# uCschematic.net
KiCad netlist of a schematic drawn in EAGLE
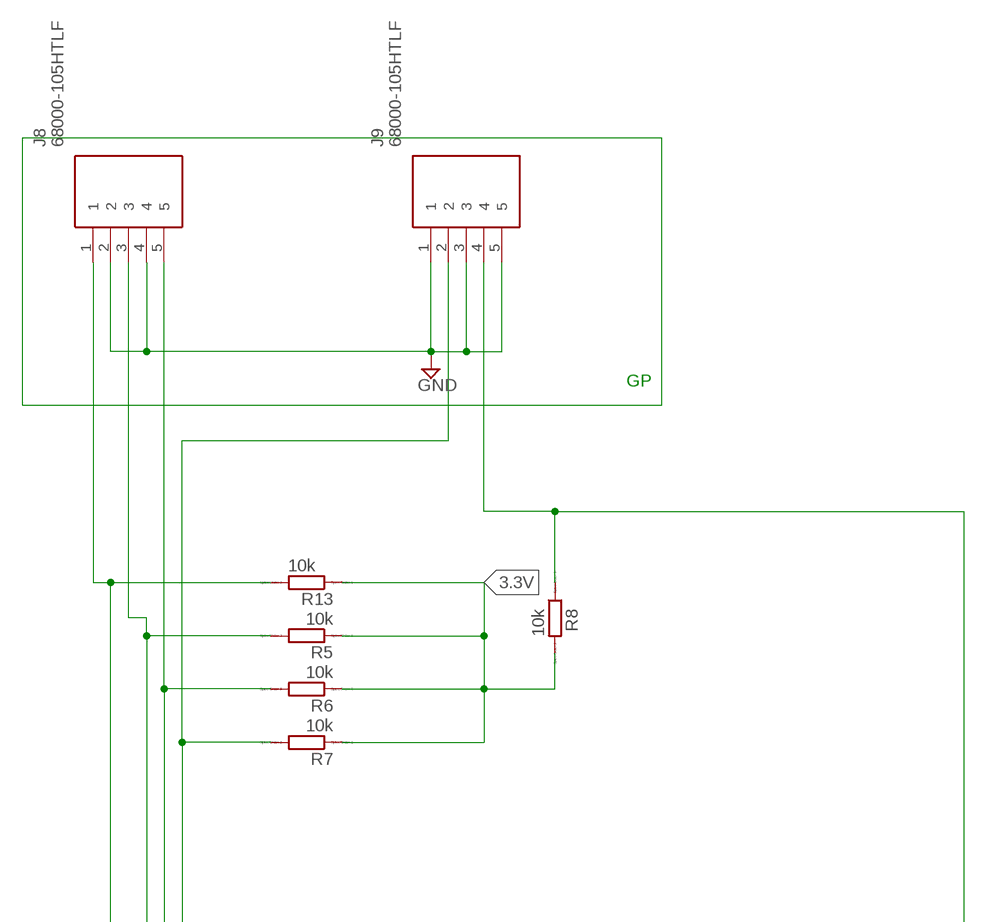
[diagram p0: schematic, sheet 1, part 1 of 3]
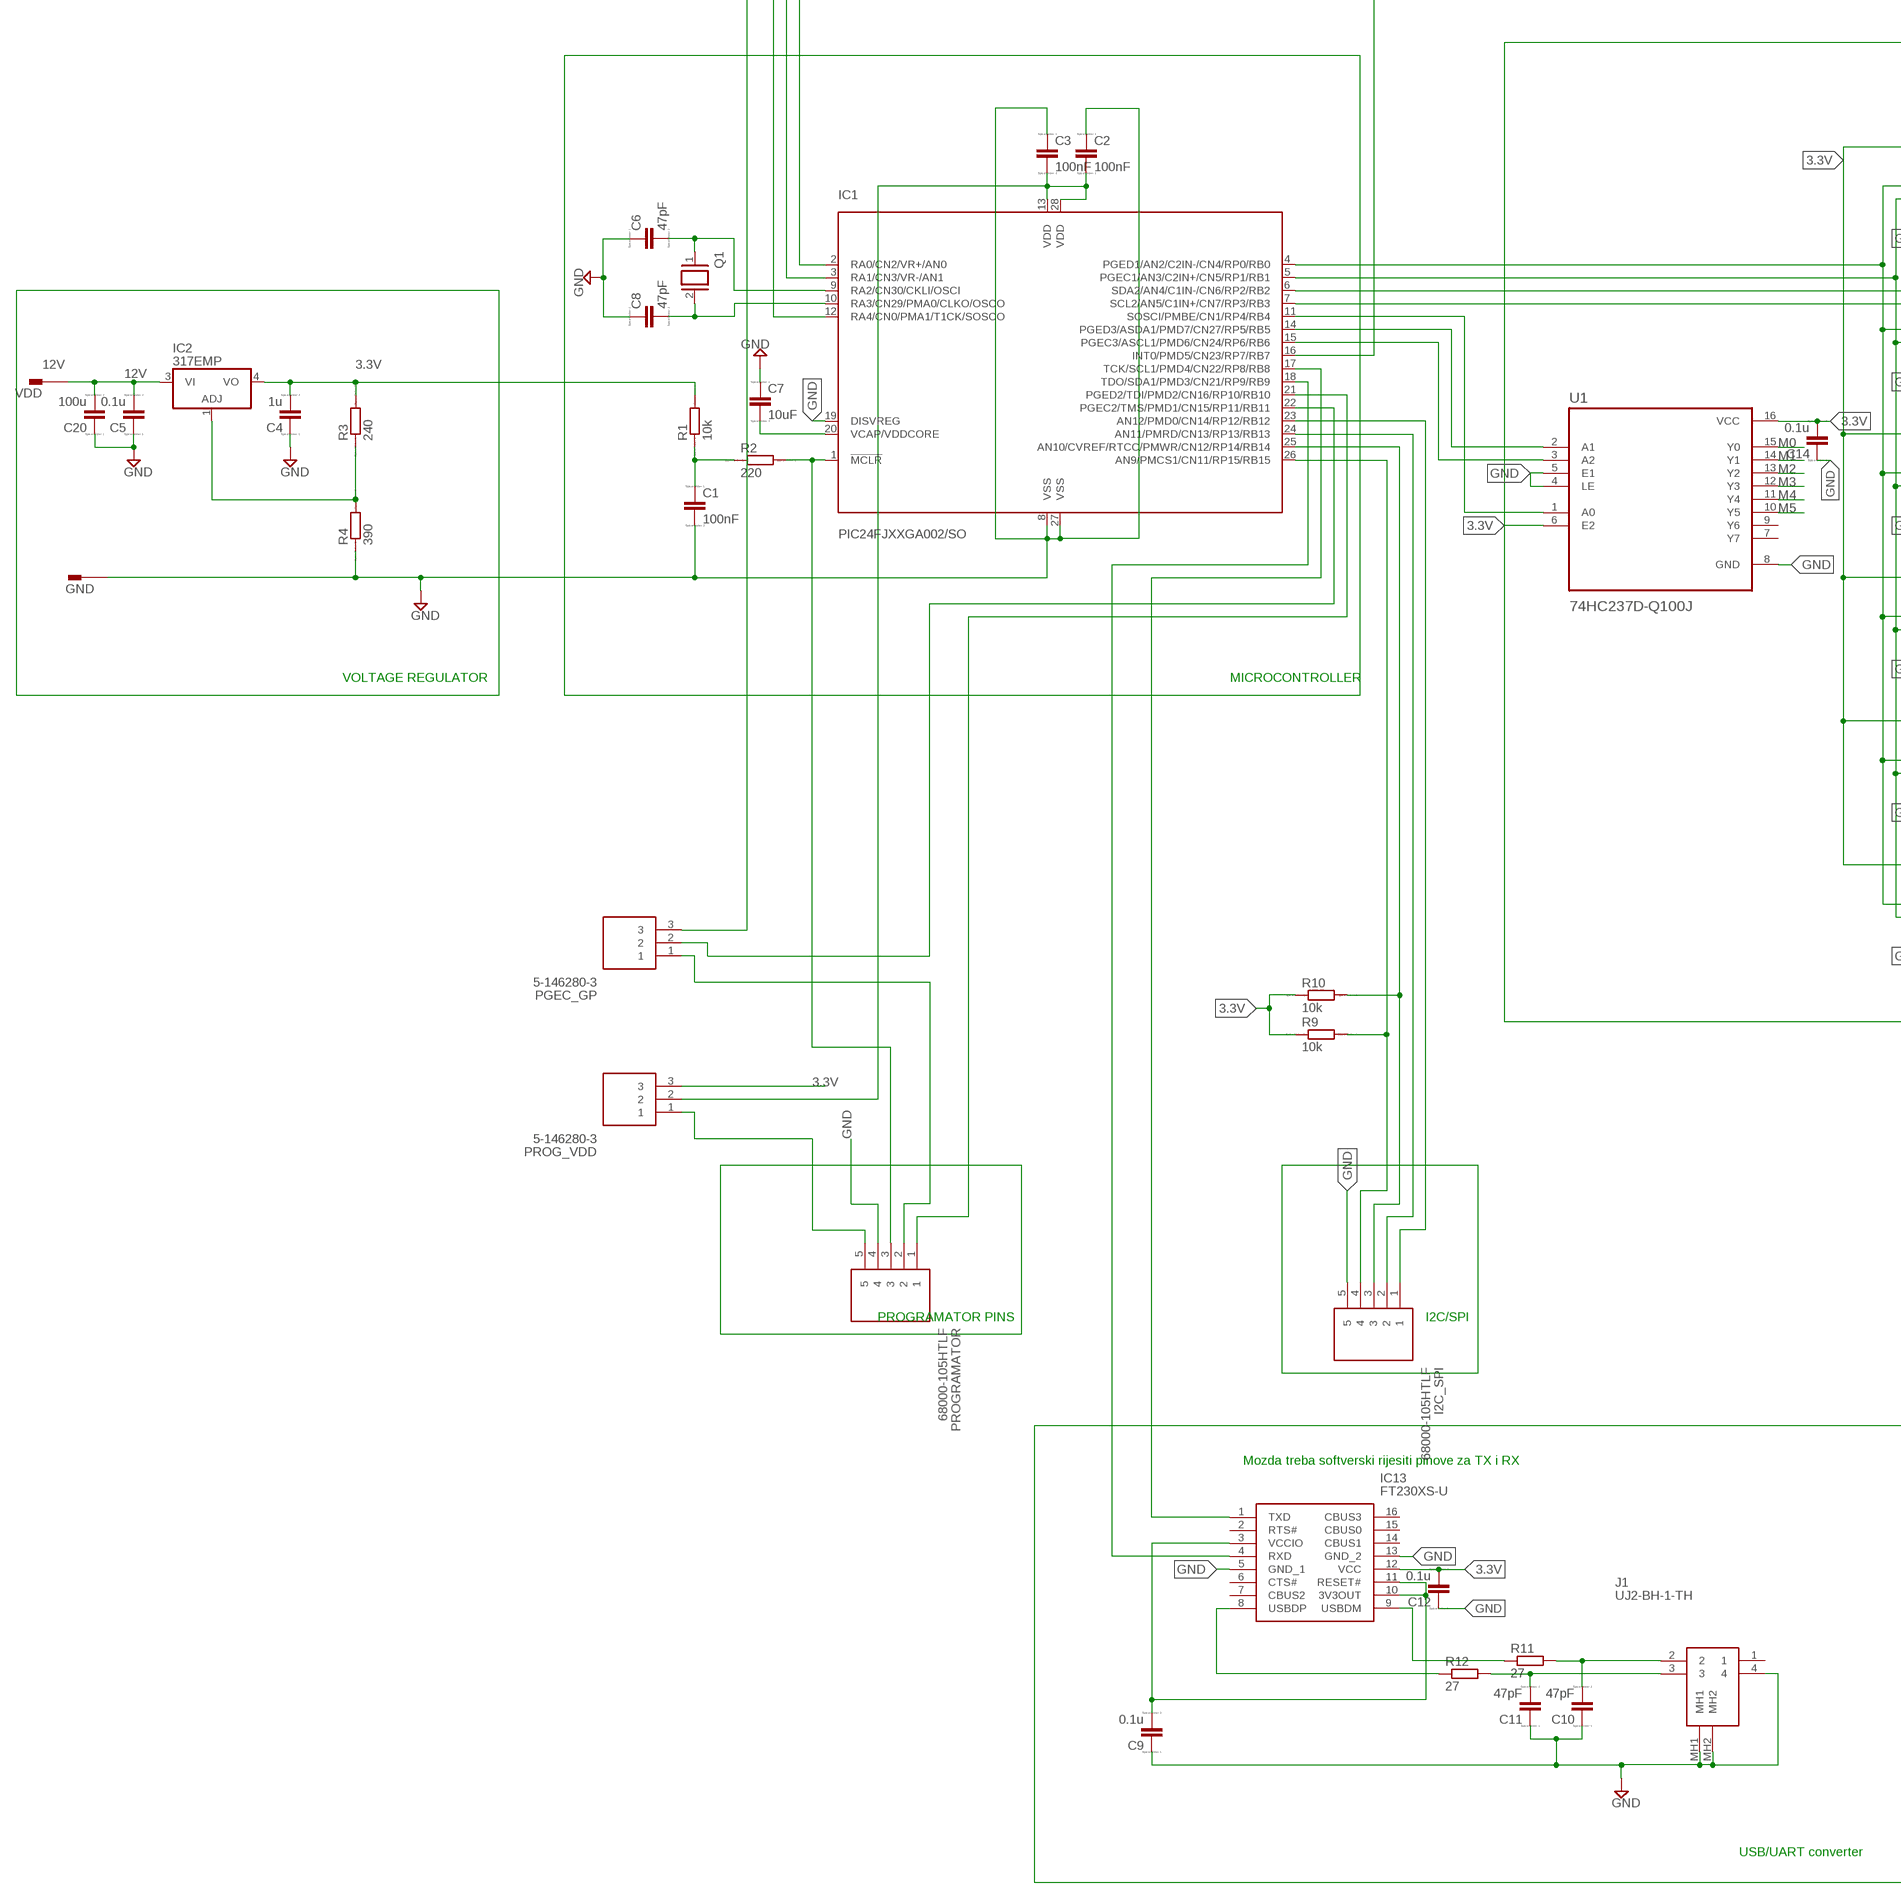
[diagram p1: schematic, sheet 1, part 2 of 3]
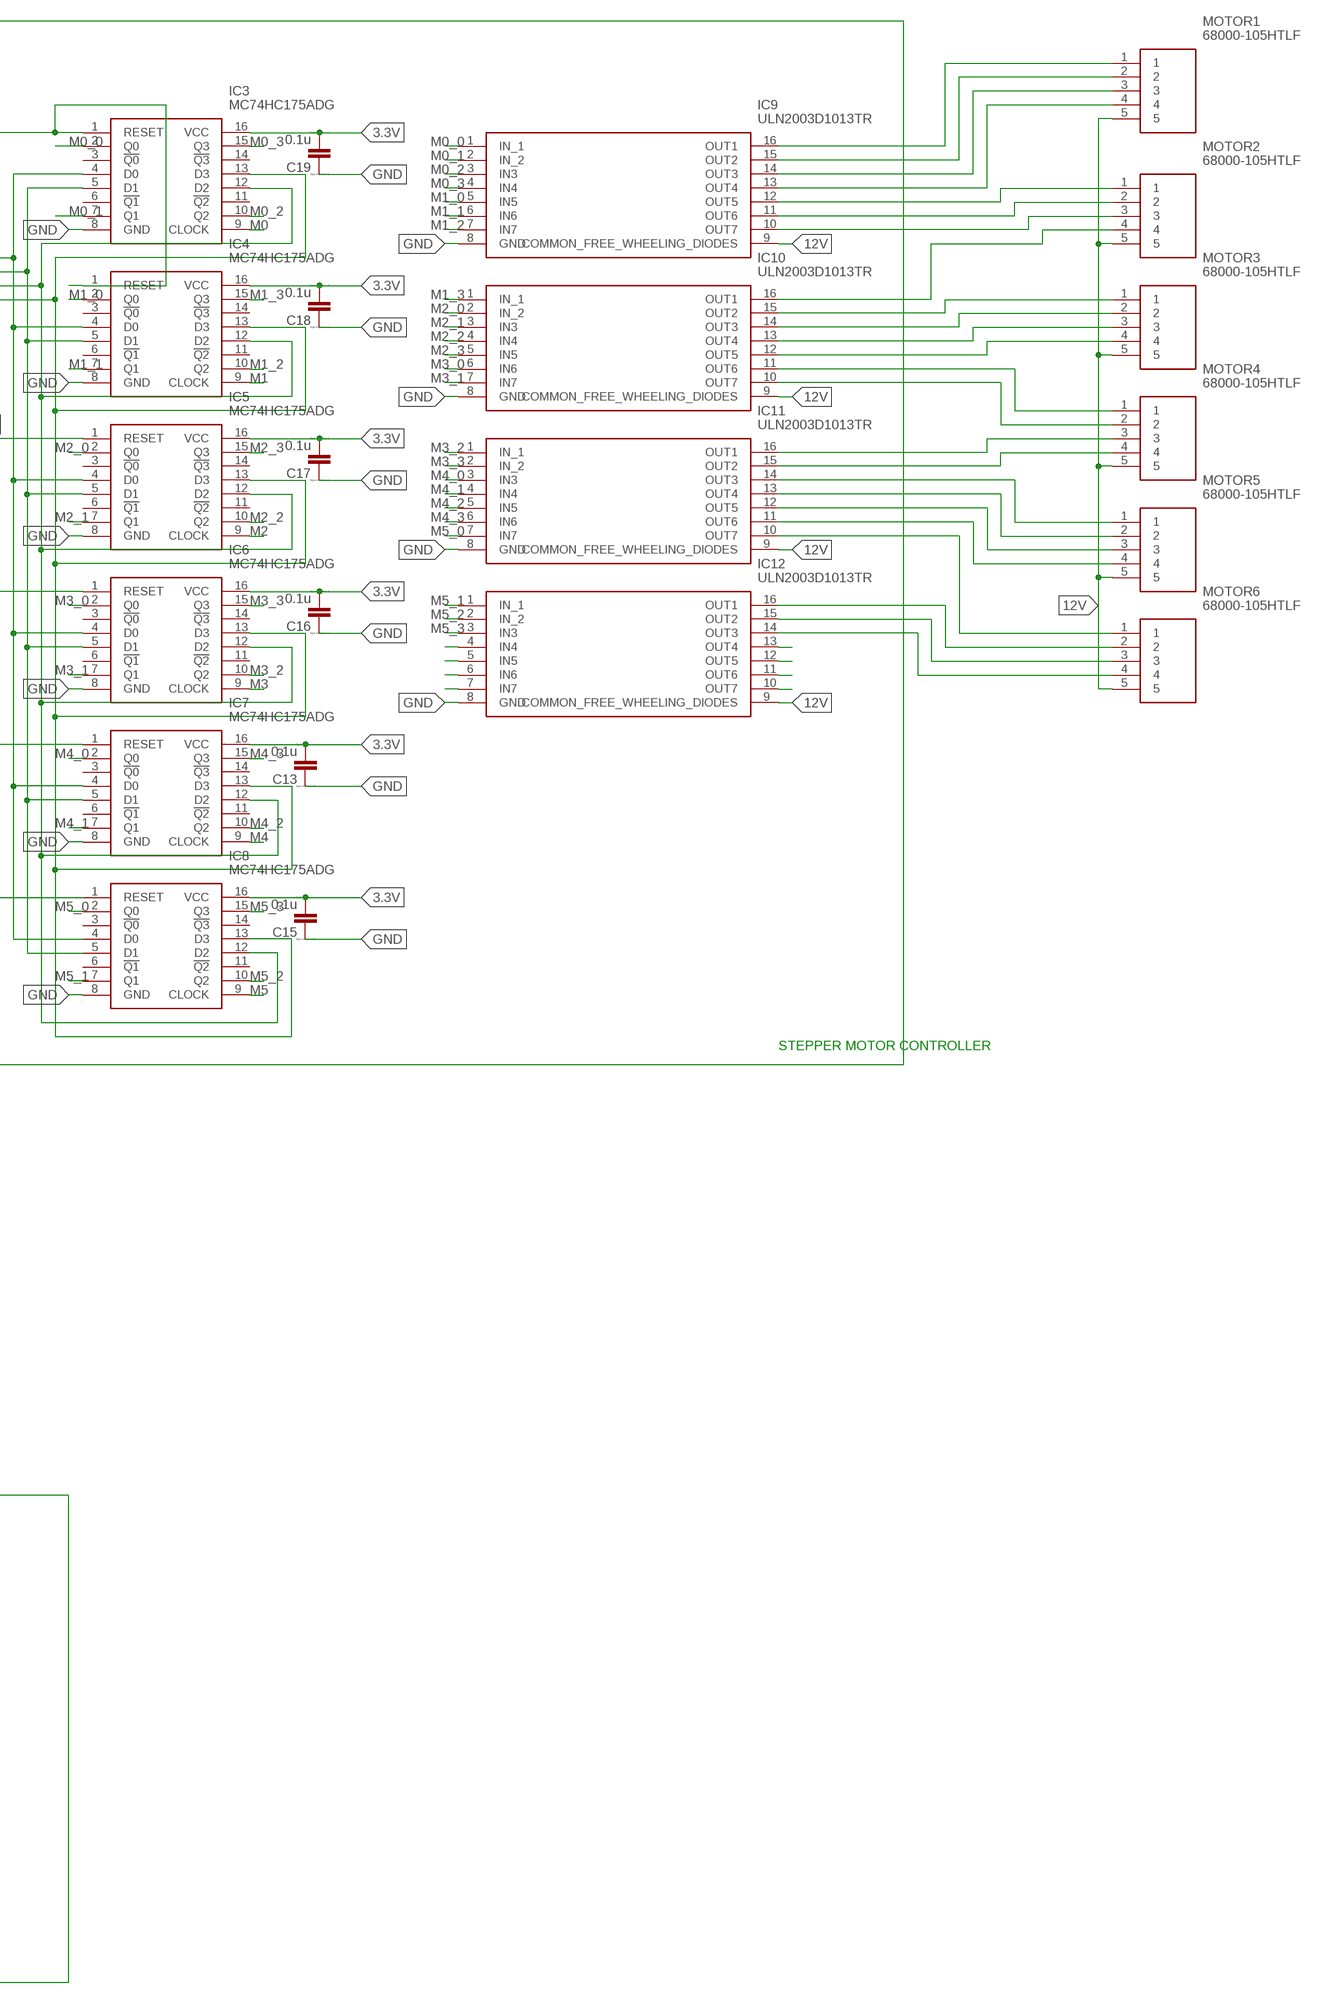
[diagram p2: schematic, sheet 1, part 3 of 3]

(export (version "E")
  (design (tool "Eeschema 10.0.6"))
  (components
    (comp (ref "C1")
      (value "100nF")
      (footprint "eagle-import:C0805")
      (libsource (lib "eagle-import") (part "C"))
    )
    (comp (ref "C2")
      (value "100nF")
      (footprint "eagle-import:C0805")
      (libsource (lib "eagle-import") (part "C"))
    )
    (comp (ref "C3")
      (value "100nF")
      (footprint "eagle-import:C0805")
      (libsource (lib "eagle-import") (part "C"))
    )
    (comp (ref "C4")
      (value "1u")
      (footprint "eagle-import:C0805")
      (libsource (lib "eagle-import") (part "C"))
    )
    (comp (ref "C5")
      (value "0.1u")
      (footprint "eagle-import:C0805")
      (libsource (lib "eagle-import") (part "C"))
    )
    (comp (ref "C6")
      (value "47pF")
      (footprint "eagle-import:C0805")
      (libsource (lib "eagle-import") (part "C"))
    )
    (comp (ref "C7")
      (value "10uF")
      (footprint "eagle-import:C0805")
      (libsource (lib "eagle-import") (part "C"))
    )
    (comp (ref "C8")
      (value "47pF")
      (footprint "eagle-import:C0805")
      (libsource (lib "eagle-import") (part "C"))
    )
    (comp (ref "C9")
      (value "0.1u")
      (footprint "eagle-import:C0805")
      (libsource (lib "eagle-import") (part "C"))
    )
    (comp (ref "C10")
      (value "47pF")
      (footprint "eagle-import:C0805")
      (libsource (lib "eagle-import") (part "C"))
    )
    (comp (ref "C11")
      (value "47pF")
      (footprint "eagle-import:C0805")
      (libsource (lib "eagle-import") (part "C"))
    )
    (comp (ref "C12")
      (value "0.1u")
      (footprint "eagle-import:C0805")
      (libsource (lib "eagle-import") (part "C"))
    )
    (comp (ref "C13")
      (value "0.1u")
      (footprint "eagle-import:C0805")
      (libsource (lib "eagle-import") (part "C"))
    )
    (comp (ref "C14")
      (value "0.1u")
      (footprint "eagle-import:C0805")
      (libsource (lib "eagle-import") (part "C"))
    )
    (comp (ref "C15")
      (value "0.1u")
      (footprint "eagle-import:C0805")
      (libsource (lib "eagle-import") (part "C"))
    )
    (comp (ref "C16")
      (value "0.1u")
      (footprint "eagle-import:C0805")
      (libsource (lib "eagle-import") (part "C"))
    )
    (comp (ref "C17")
      (value "0.1u")
      (footprint "eagle-import:C0805")
      (libsource (lib "eagle-import") (part "C"))
    )
    (comp (ref "C18")
      (value "0.1u")
      (footprint "eagle-import:C0805")
      (libsource (lib "eagle-import") (part "C"))
    )
    (comp (ref "C19")
      (value "0.1u")
      (footprint "eagle-import:C0805")
      (libsource (lib "eagle-import") (part "C"))
    )
    (comp (ref "C20")
      (value "100u")
      (footprint "eagle-import:C0805")
      (libsource (lib "eagle-import") (part "C"))
    )
    (comp (ref "GND")
      (value "PIN1-2")
      (footprint "eagle-import:62221")
      (fields (field (name "MF") "TYCO ELECTRONICS") (field (name "MPN") "62221-1"))
      (libsource (lib "eagle-import") (part "PIN1-2"))
    )
    (comp (ref "I2C_SPI")
      (value "68000-105HTLF")
      (footprint "eagle-import:HDRV5W67P0X254_1X5_1270X241X85")
      (fields (field (name "MOUSER_PART_NUMBER") "649-68000-105HTLF"))
      (libsource (lib "eagle-import") (part "68000-105HTLF"))
    )
    (comp (ref "IC1")
      (value "PIC24FJXXGA002/SO")
      (footprint "eagle-import:SO28W")
      (libsource (lib "eagle-import") (part "PIC24FJXXGA002/SO"))
    )
    (comp (ref "IC2")
      (value "317EMP")
      (footprint "eagle-import:SOT223")
      (libsource (lib "eagle-import") (part "317EMP"))
    )
    (comp (ref "IC3")
      (value "MC74HC175ADG")
      (footprint "eagle-import:SOIC127P600X175-16N")
      (fields (field (name "MOUSER_PART_NUMBER") "863-MC74HC175ADG"))
      (libsource (lib "eagle-import") (part "MC74HC175ADG"))
    )
    (comp (ref "IC4")
      (value "MC74HC175ADG")
      (footprint "eagle-import:SOIC127P600X175-16N")
      (fields (field (name "MOUSER_PART_NUMBER") "863-MC74HC175ADG"))
      (libsource (lib "eagle-import") (part "MC74HC175ADG"))
    )
    (comp (ref "IC5")
      (value "MC74HC175ADG")
      (footprint "eagle-import:SOIC127P600X175-16N")
      (fields (field (name "MOUSER_PART_NUMBER") "863-MC74HC175ADG"))
      (libsource (lib "eagle-import") (part "MC74HC175ADG"))
    )
    (comp (ref "IC6")
      (value "MC74HC175ADG")
      (footprint "eagle-import:SOIC127P600X175-16N")
      (fields (field (name "MOUSER_PART_NUMBER") "863-MC74HC175ADG"))
      (libsource (lib "eagle-import") (part "MC74HC175ADG"))
    )
    (comp (ref "IC7")
      (value "MC74HC175ADG")
      (footprint "eagle-import:SOIC127P600X175-16N")
      (fields (field (name "MOUSER_PART_NUMBER") "863-MC74HC175ADG"))
      (libsource (lib "eagle-import") (part "MC74HC175ADG"))
    )
    (comp (ref "IC8")
      (value "MC74HC175ADG")
      (footprint "eagle-import:SOIC127P600X175-16N")
      (fields (field (name "MOUSER_PART_NUMBER") "863-MC74HC175ADG"))
      (libsource (lib "eagle-import") (part "MC74HC175ADG"))
    )
    (comp (ref "IC9")
      (value "ULN2003D1013TR")
      (footprint "eagle-import:SOIC127P600X175-16N")
      (fields (field (name "MOUSER_PART_NUMBER") "511-ULN2003D1013TR"))
      (libsource (lib "eagle-import") (part "ULN2003D1013TR"))
    )
    (comp (ref "IC10")
      (value "ULN2003D1013TR")
      (footprint "eagle-import:SOIC127P600X175-16N")
      (fields (field (name "MOUSER_PART_NUMBER") "511-ULN2003D1013TR"))
      (libsource (lib "eagle-import") (part "ULN2003D1013TR"))
    )
    (comp (ref "IC11")
      (value "ULN2003D1013TR")
      (footprint "eagle-import:SOIC127P600X175-16N")
      (fields (field (name "MOUSER_PART_NUMBER") "511-ULN2003D1013TR"))
      (libsource (lib "eagle-import") (part "ULN2003D1013TR"))
    )
    (comp (ref "IC12")
      (value "ULN2003D1013TR")
      (footprint "eagle-import:SOIC127P600X175-16N")
      (fields (field (name "MOUSER_PART_NUMBER") "511-ULN2003D1013TR"))
      (libsource (lib "eagle-import") (part "ULN2003D1013TR"))
    )
    (comp (ref "IC13")
      (value "FT230XS-U")
      (footprint "eagle-import:SOP64P599X175-16N")
      (fields (field (name "MOUSER_PART_NUMBER") "895-FT230XS-U"))
      (libsource (lib "eagle-import") (part "FT230XS-U"))
    )
    (comp (ref "J1")
      (value "UJ2-BH-1-TH")
      (footprint "eagle-import:UJ2BH1TH")
      (fields (field (name "MOUSER_PART_NUMBER") "490-UJ2-BH-1-TH"))
      (libsource (lib "eagle-import") (part "UJ2-BH-1-TH"))
    )
    (comp (ref "J8")
      (value "68000-105HTLF")
      (footprint "eagle-import:HDRV5W67P0X254_1X5_1270X241X85")
      (fields (field (name "MOUSER_PART_NUMBER") "649-68000-105HTLF"))
      (libsource (lib "eagle-import") (part "68000-105HTLF"))
    )
    (comp (ref "J9")
      (value "68000-105HTLF")
      (footprint "eagle-import:HDRV5W67P0X254_1X5_1270X241X85")
      (fields (field (name "MOUSER_PART_NUMBER") "649-68000-105HTLF"))
      (libsource (lib "eagle-import") (part "68000-105HTLF"))
    )
    (comp (ref "MOTOR1")
      (value "68000-105HTLF")
      (footprint "eagle-import:HDRV5W67P0X254_1X5_1270X241X85")
      (fields (field (name "MOUSER_PART_NUMBER") "649-68000-105HTLF"))
      (libsource (lib "eagle-import") (part "68000-105HTLF"))
    )
    (comp (ref "MOTOR2")
      (value "68000-105HTLF")
      (footprint "eagle-import:HDRV5W67P0X254_1X5_1270X241X85")
      (fields (field (name "MOUSER_PART_NUMBER") "649-68000-105HTLF"))
      (libsource (lib "eagle-import") (part "68000-105HTLF"))
    )
    (comp (ref "MOTOR3")
      (value "68000-105HTLF")
      (footprint "eagle-import:HDRV5W67P0X254_1X5_1270X241X85")
      (fields (field (name "MOUSER_PART_NUMBER") "649-68000-105HTLF"))
      (libsource (lib "eagle-import") (part "68000-105HTLF"))
    )
    (comp (ref "MOTOR4")
      (value "68000-105HTLF")
      (footprint "eagle-import:HDRV5W67P0X254_1X5_1270X241X85")
      (fields (field (name "MOUSER_PART_NUMBER") "649-68000-105HTLF"))
      (libsource (lib "eagle-import") (part "68000-105HTLF"))
    )
    (comp (ref "MOTOR5")
      (value "68000-105HTLF")
      (footprint "eagle-import:HDRV5W67P0X254_1X5_1270X241X85")
      (fields (field (name "MOUSER_PART_NUMBER") "649-68000-105HTLF"))
      (libsource (lib "eagle-import") (part "68000-105HTLF"))
    )
    (comp (ref "MOTOR6")
      (value "68000-105HTLF")
      (footprint "eagle-import:HDRV5W67P0X254_1X5_1270X241X85")
      (fields (field (name "MOUSER_PART_NUMBER") "649-68000-105HTLF"))
      (libsource (lib "eagle-import") (part "68000-105HTLF"))
    )
    (comp (ref "PGEC_GP")
      (value "5-146280-3")
      (footprint "eagle-import:HDRV3W97P0X254_1X3_721X234X821")
      (fields (field (name "MOUSER_PART_NUMBER") "571-5-146280-3"))
      (libsource (lib "eagle-import") (part "5-146280-3"))
    )
    (comp (ref "PROGRAMATOR")
      (value "68000-105HTLF")
      (footprint "eagle-import:HDRV5W67P0X254_1X5_1270X241X85")
      (fields (field (name "MOUSER_PART_NUMBER") "649-68000-105HTLF"))
      (libsource (lib "eagle-import") (part "68000-105HTLF"))
    )
    (comp (ref "PROG_VDD")
      (value "5-146280-3")
      (footprint "eagle-import:HDRV3W97P0X254_1X3_721X234X821")
      (fields (field (name "MOUSER_PART_NUMBER") "571-5-146280-3"))
      (libsource (lib "eagle-import") (part "5-146280-3"))
    )
    (comp (ref "Q1")
      (value "XTAL/S")
      (footprint "eagle-import:QS")
      (libsource (lib "eagle-import") (part "XTAL/S"))
    )
    (comp (ref "R1")
      (value "10k")
      (footprint "eagle-import:R0805")
      (libsource (lib "eagle-import") (part "R"))
    )
    (comp (ref "R2")
      (value "220")
      (footprint "eagle-import:R0805")
      (libsource (lib "eagle-import") (part "R"))
    )
    (comp (ref "R3")
      (value "240")
      (footprint "eagle-import:R0805")
      (libsource (lib "eagle-import") (part "R"))
    )
    (comp (ref "R4")
      (value "390")
      (footprint "eagle-import:R0805")
      (libsource (lib "eagle-import") (part "R"))
    )
    (comp (ref "R5")
      (value "10k")
      (footprint "eagle-import:R0805")
      (libsource (lib "eagle-import") (part "R"))
    )
    (comp (ref "R6")
      (value "10k")
      (footprint "eagle-import:R0805")
      (libsource (lib "eagle-import") (part "R"))
    )
    (comp (ref "R7")
      (value "10k")
      (footprint "eagle-import:R0805")
      (libsource (lib "eagle-import") (part "R"))
    )
    (comp (ref "R8")
      (value "10k")
      (footprint "eagle-import:R0805")
      (libsource (lib "eagle-import") (part "R"))
    )
    (comp (ref "R9")
      (value "10k")
      (footprint "eagle-import:R0805")
      (libsource (lib "eagle-import") (part "R"))
    )
    (comp (ref "R10")
      (value "10k")
      (footprint "eagle-import:R0805")
      (libsource (lib "eagle-import") (part "R"))
    )
    (comp (ref "R11")
      (value "27")
      (footprint "eagle-import:R0805")
      (libsource (lib "eagle-import") (part "R-EU_R0805"))
    )
    (comp (ref "R12")
      (value "27")
      (footprint "eagle-import:R0805")
      (libsource (lib "eagle-import") (part "R-EU_R0805"))
    )
    (comp (ref "R13")
      (value "10k")
      (footprint "eagle-import:R0805")
      (libsource (lib "eagle-import") (part "R"))
    )
    (comp (ref "U1")
      (value "74HC237D-Q100J")
      (footprint "eagle-import:SOIC127P600X175-16N")
      (fields (field (name "MF") "Nexperia USA Inc."))
      (libsource (lib "eagle-import") (part "74HC237D-Q100J"))
    )
    (comp (ref "VDD")
      (value "12V")
      (footprint "eagle-import:62221")
      (fields (field (name "MF") "TYCO ELECTRONICS") (field (name "MPN") "62221-1"))
      (libsource (lib "eagle-import") (part "PIN1-2"))
    )
  )
  (nets
    (net (code "1") (name "/M0") (class "Default")
      (node (ref "IC3") (pin "9") (pinfunction "CLOCK_9") (pintype "bidirectional"))
      (node (ref "U1") (pin "15") (pinfunction "Y0_15") (pintype "output"))
    )
    (net (code "2") (name "/M0_0") (class "Default")
      (node (ref "IC3") (pin "2") (pinfunction "Q0_2") (pintype "bidirectional"))
      (node (ref "IC9") (pin "1") (pinfunction "IN_1_1") (pintype "bidirectional"))
    )
    (net (code "3") (name "/M0_1") (class "Default")
      (node (ref "IC3") (pin "7") (pinfunction "Q1_7") (pintype "bidirectional"))
      (node (ref "IC9") (pin "2") (pinfunction "IN_2_2") (pintype "bidirectional"))
    )
    (net (code "4") (name "/M0_2") (class "Default")
      (node (ref "IC3") (pin "10") (pinfunction "Q2_10") (pintype "bidirectional"))
      (node (ref "IC9") (pin "3") (pinfunction "IN3_3") (pintype "bidirectional"))
    )
    (net (code "5") (name "/M0_3") (class "Default")
      (node (ref "IC3") (pin "15") (pinfunction "Q3_15") (pintype "bidirectional"))
      (node (ref "IC9") (pin "4") (pinfunction "IN4_4") (pintype "bidirectional"))
    )
    (net (code "6") (name "/M1") (class "Default")
      (node (ref "IC4") (pin "9") (pinfunction "CLOCK_9") (pintype "bidirectional"))
      (node (ref "U1") (pin "14") (pinfunction "Y1_14") (pintype "output"))
    )
    (net (code "7") (name "/M1_0") (class "Default")
      (node (ref "IC4") (pin "2") (pinfunction "Q0_2") (pintype "bidirectional"))
      (node (ref "IC9") (pin "5") (pinfunction "IN5_5") (pintype "bidirectional"))
    )
    (net (code "8") (name "/M1_1") (class "Default")
      (node (ref "IC4") (pin "7") (pinfunction "Q1_7") (pintype "bidirectional"))
      (node (ref "IC9") (pin "6") (pinfunction "IN6_6") (pintype "bidirectional"))
    )
    (net (code "9") (name "/M1_2") (class "Default")
      (node (ref "IC4") (pin "10") (pinfunction "Q2_10") (pintype "bidirectional"))
      (node (ref "IC9") (pin "7") (pinfunction "IN7_7") (pintype "bidirectional"))
    )
    (net (code "10") (name "/M1_3") (class "Default")
      (node (ref "IC10") (pin "1") (pinfunction "IN_1_1") (pintype "bidirectional"))
      (node (ref "IC4") (pin "15") (pinfunction "Q3_15") (pintype "bidirectional"))
    )
    (net (code "11") (name "/M2") (class "Default")
      (node (ref "IC5") (pin "9") (pinfunction "CLOCK_9") (pintype "bidirectional"))
      (node (ref "U1") (pin "13") (pinfunction "Y2_13") (pintype "output"))
    )
    (net (code "12") (name "/M2_0") (class "Default")
      (node (ref "IC10") (pin "2") (pinfunction "IN_2_2") (pintype "bidirectional"))
      (node (ref "IC5") (pin "2") (pinfunction "Q0_2") (pintype "bidirectional"))
    )
    (net (code "13") (name "/M2_1") (class "Default")
      (node (ref "IC10") (pin "3") (pinfunction "IN3_3") (pintype "bidirectional"))
      (node (ref "IC5") (pin "7") (pinfunction "Q1_7") (pintype "bidirectional"))
    )
    (net (code "14") (name "/M2_2") (class "Default")
      (node (ref "IC10") (pin "4") (pinfunction "IN4_4") (pintype "bidirectional"))
      (node (ref "IC5") (pin "10") (pinfunction "Q2_10") (pintype "bidirectional"))
    )
    (net (code "15") (name "/M2_3") (class "Default")
      (node (ref "IC10") (pin "5") (pinfunction "IN5_5") (pintype "bidirectional"))
      (node (ref "IC5") (pin "15") (pinfunction "Q3_15") (pintype "bidirectional"))
    )
    (net (code "16") (name "/M3") (class "Default")
      (node (ref "IC6") (pin "9") (pinfunction "CLOCK_9") (pintype "bidirectional"))
      (node (ref "U1") (pin "12") (pinfunction "Y3_12") (pintype "output"))
    )
    (net (code "17") (name "/M3_0") (class "Default")
      (node (ref "IC10") (pin "6") (pinfunction "IN6_6") (pintype "bidirectional"))
      (node (ref "IC6") (pin "2") (pinfunction "Q0_2") (pintype "bidirectional"))
    )
    (net (code "18") (name "/M3_1") (class "Default")
      (node (ref "IC10") (pin "7") (pinfunction "IN7_7") (pintype "bidirectional"))
      (node (ref "IC6") (pin "7") (pinfunction "Q1_7") (pintype "bidirectional"))
    )
    (net (code "19") (name "/M3_2") (class "Default")
      (node (ref "IC11") (pin "1") (pinfunction "IN_1_1") (pintype "bidirectional"))
      (node (ref "IC6") (pin "10") (pinfunction "Q2_10") (pintype "bidirectional"))
    )
    (net (code "20") (name "/M3_3") (class "Default")
      (node (ref "IC11") (pin "2") (pinfunction "IN_2_2") (pintype "bidirectional"))
      (node (ref "IC6") (pin "15") (pinfunction "Q3_15") (pintype "bidirectional"))
    )
    (net (code "21") (name "/M4") (class "Default")
      (node (ref "IC7") (pin "9") (pinfunction "CLOCK_9") (pintype "bidirectional"))
      (node (ref "U1") (pin "11") (pinfunction "Y4_11") (pintype "output"))
    )
    (net (code "22") (name "/M4_0") (class "Default")
      (node (ref "IC11") (pin "3") (pinfunction "IN3_3") (pintype "bidirectional"))
      (node (ref "IC7") (pin "2") (pinfunction "Q0_2") (pintype "bidirectional"))
    )
    (net (code "23") (name "/M4_1") (class "Default")
      (node (ref "IC11") (pin "4") (pinfunction "IN4_4") (pintype "bidirectional"))
      (node (ref "IC7") (pin "7") (pinfunction "Q1_7") (pintype "bidirectional"))
    )
    (net (code "24") (name "/M4_2") (class "Default")
      (node (ref "IC11") (pin "5") (pinfunction "IN5_5") (pintype "bidirectional"))
      (node (ref "IC7") (pin "10") (pinfunction "Q2_10") (pintype "bidirectional"))
    )
    (net (code "25") (name "/M4_3") (class "Default")
      (node (ref "IC11") (pin "6") (pinfunction "IN6_6") (pintype "bidirectional"))
      (node (ref "IC7") (pin "15") (pinfunction "Q3_15") (pintype "bidirectional"))
    )
    (net (code "26") (name "/M5") (class "Default")
      (node (ref "IC8") (pin "9") (pinfunction "CLOCK_9") (pintype "bidirectional"))
      (node (ref "U1") (pin "10") (pinfunction "Y5_10") (pintype "output"))
    )
    (net (code "27") (name "/M5_0") (class "Default")
      (node (ref "IC11") (pin "7") (pinfunction "IN7_7") (pintype "bidirectional"))
      (node (ref "IC8") (pin "2") (pinfunction "Q0_2") (pintype "bidirectional"))
    )
    (net (code "28") (name "/M5_1") (class "Default")
      (node (ref "IC12") (pin "1") (pinfunction "IN_1_1") (pintype "bidirectional"))
      (node (ref "IC8") (pin "7") (pinfunction "Q1_7") (pintype "bidirectional"))
    )
    (net (code "29") (name "/M5_2") (class "Default")
      (node (ref "IC12") (pin "2") (pinfunction "IN_2_2") (pintype "bidirectional"))
      (node (ref "IC8") (pin "10") (pinfunction "Q2_10") (pintype "bidirectional"))
    )
    (net (code "30") (name "/M5_3") (class "Default")
      (node (ref "IC12") (pin "3") (pinfunction "IN3_3") (pintype "bidirectional"))
      (node (ref "IC8") (pin "15") (pinfunction "Q3_15") (pintype "bidirectional"))
    )
    (net (code "31") (name "3.3V") (class "Default")
      (node (ref "C12") (pin "2") (pinfunction "2_2") (pintype "passive"))
      (node (ref "C13") (pin "2") (pinfunction "2_2") (pintype "passive"))
      (node (ref "C14") (pin "2") (pinfunction "2_2") (pintype "passive"))
      (node (ref "C15") (pin "2") (pinfunction "2_2") (pintype "passive"))
      (node (ref "C16") (pin "2") (pinfunction "2_2") (pintype "passive"))
      (node (ref "C17") (pin "2") (pinfunction "2_2") (pintype "passive"))
      (node (ref "C18") (pin "2") (pinfunction "2_2") (pintype "passive"))
      (node (ref "C19") (pin "2") (pinfunction "2_2") (pintype "passive"))
      (node (ref "C4") (pin "2") (pinfunction "2_2") (pintype "passive"))
      (node (ref "IC13") (pin "12") (pinfunction "VCC_12") (pintype "bidirectional"))
      (node (ref "IC2") (pin "4") (pinfunction "VO_4") (pintype "passive"))
      (node (ref "IC3") (pin "1") (pinfunction "RESET_1") (pintype "bidirectional"))
      (node (ref "IC3") (pin "16") (pinfunction "VCC_16") (pintype "bidirectional"))
      (node (ref "IC4") (pin "1") (pinfunction "RESET_1") (pintype "bidirectional"))
      (node (ref "IC4") (pin "16") (pinfunction "VCC_16") (pintype "bidirectional"))
      (node (ref "IC5") (pin "1") (pinfunction "RESET_1") (pintype "bidirectional"))
      (node (ref "IC5") (pin "16") (pinfunction "VCC_16") (pintype "bidirectional"))
      (node (ref "IC6") (pin "1") (pinfunction "RESET_1") (pintype "bidirectional"))
      (node (ref "IC6") (pin "16") (pinfunction "VCC_16") (pintype "bidirectional"))
      (node (ref "IC7") (pin "1") (pinfunction "RESET_1") (pintype "bidirectional"))
      (node (ref "IC7") (pin "16") (pinfunction "VCC_16") (pintype "bidirectional"))
      (node (ref "IC8") (pin "1") (pinfunction "RESET_1") (pintype "bidirectional"))
      (node (ref "IC8") (pin "16") (pinfunction "VCC_16") (pintype "bidirectional"))
      (node (ref "PROG_VDD") (pin "3") (pinfunction "3_3") (pintype "bidirectional"))
      (node (ref "R1") (pin "2") (pinfunction "2_2") (pintype "passive"))
      (node (ref "R10") (pin "1") (pinfunction "1_1") (pintype "passive"))
      (node (ref "R13") (pin "1") (pinfunction "1_1") (pintype "passive"))
      (node (ref "R3") (pin "2") (pinfunction "2_2") (pintype "passive"))
      (node (ref "R5") (pin "1") (pinfunction "1_1") (pintype "passive"))
      (node (ref "R6") (pin "1") (pinfunction "1_1") (pintype "passive"))
      (node (ref "R7") (pin "1") (pinfunction "1_1") (pintype "passive"))
      (node (ref "R8") (pin "2") (pinfunction "2_2") (pintype "passive"))
      (node (ref "R9") (pin "1") (pinfunction "1_1") (pintype "passive"))
      (node (ref "U1") (pin "16") (pinfunction "VCC_16") (pintype "power_in"))
      (node (ref "U1") (pin "6") (pinfunction "E2_6") (pintype "input"))
    )
    (net (code "32") (name "12V") (class "Default")
      (node (ref "C20") (pin "2") (pinfunction "2_2") (pintype "passive"))
      (node (ref "C5") (pin "2") (pinfunction "2_2") (pintype "passive"))
      (node (ref "IC10") (pin "9") (pinfunction "COMMON_FREE_WHEELING_DIODES_9") (pintype "bidirectional"))
      (node (ref "IC11") (pin "9") (pinfunction "COMMON_FREE_WHEELING_DIODES_9") (pintype "bidirectional"))
      (node (ref "IC12") (pin "9") (pinfunction "COMMON_FREE_WHEELING_DIODES_9") (pintype "bidirectional"))
      (node (ref "IC2") (pin "3") (pinfunction "VI_3") (pintype "input"))
      (node (ref "IC9") (pin "9") (pinfunction "COMMON_FREE_WHEELING_DIODES_9") (pintype "bidirectional"))
      (node (ref "MOTOR1") (pin "5") (pinfunction "5_5") (pintype "bidirectional"))
      (node (ref "MOTOR2") (pin "5") (pinfunction "5_5") (pintype "bidirectional"))
      (node (ref "MOTOR3") (pin "5") (pinfunction "5_5") (pintype "bidirectional"))
      (node (ref "MOTOR4") (pin "5") (pinfunction "5_5") (pintype "bidirectional"))
      (node (ref "MOTOR5") (pin "5") (pinfunction "5_5") (pintype "bidirectional"))
      (node (ref "MOTOR6") (pin "5") (pinfunction "5_5") (pintype "bidirectional"))
      (node (ref "VDD") (pin "1") (pinfunction "1_1") (pintype "passive"))
    )
    (net (code "33") (name "GND") (class "Default")
      (node (ref "C1") (pin "2") (pinfunction "2_2") (pintype "passive"))
      (node (ref "C10") (pin "1") (pinfunction "1_1") (pintype "passive"))
      (node (ref "C11") (pin "1") (pinfunction "1_1") (pintype "passive"))
      (node (ref "C12") (pin "1") (pinfunction "1_1") (pintype "passive"))
      (node (ref "C14") (pin "1") (pinfunction "1_1") (pintype "passive"))
      (node (ref "C2") (pin "1") (pinfunction "1_1") (pintype "passive"))
      (node (ref "C20") (pin "1") (pinfunction "1_1") (pintype "passive"))
      (node (ref "C3") (pin "1") (pinfunction "1_1") (pintype "passive"))
      (node (ref "C4") (pin "1") (pinfunction "1_1") (pintype "passive"))
      (node (ref "C5") (pin "1") (pinfunction "1_1") (pintype "passive"))
      (node (ref "C6") (pin "1") (pinfunction "1_1") (pintype "passive"))
      (node (ref "C7") (pin "1") (pinfunction "1_1") (pintype "passive"))
      (node (ref "C8") (pin "1") (pinfunction "1_1") (pintype "passive"))
      (node (ref "C9") (pin "1") (pinfunction "1_1") (pintype "passive"))
      (node (ref "GND") (pin "1") (pinfunction "1_1") (pintype "passive"))
      (node (ref "I2C_SPI") (pin "5") (pinfunction "5_5") (pintype "bidirectional"))
      (node (ref "IC1") (pin "19") (pinfunction "DISVREG_19") (pintype "input"))
      (node (ref "IC1") (pin "27") (pinfunction "VSS_27") (pintype "power_in"))
      (node (ref "IC1") (pin "8") (pinfunction "VSS_8") (pintype "power_in"))
      (node (ref "IC10") (pin "8") (pinfunction "GND_8") (pintype "bidirectional"))
      (node (ref "IC11") (pin "8") (pinfunction "GND_8") (pintype "bidirectional"))
      (node (ref "IC12") (pin "8") (pinfunction "GND_8") (pintype "bidirectional"))
      (node (ref "IC13") (pin "13") (pinfunction "GND_2_13") (pintype "bidirectional"))
      (node (ref "IC13") (pin "5") (pinfunction "GND_1_5") (pintype "bidirectional"))
      (node (ref "IC3") (pin "8") (pinfunction "GND_8") (pintype "bidirectional"))
      (node (ref "IC4") (pin "8") (pinfunction "GND_8") (pintype "bidirectional"))
      (node (ref "IC5") (pin "8") (pinfunction "GND_8") (pintype "bidirectional"))
      (node (ref "IC6") (pin "8") (pinfunction "GND_8") (pintype "bidirectional"))
      (node (ref "IC7") (pin "8") (pinfunction "GND_8") (pintype "bidirectional"))
      (node (ref "IC8") (pin "8") (pinfunction "GND_8") (pintype "bidirectional"))
      (node (ref "IC9") (pin "8") (pinfunction "GND_8") (pintype "bidirectional"))
      (node (ref "J1") (pin "4") (pinfunction "4_4") (pintype "bidirectional"))
      (node (ref "J1") (pin "MH1") (pinfunction "MH1_MH1") (pintype "bidirectional"))
      (node (ref "J1") (pin "MH2") (pinfunction "MH2_MH2") (pintype "bidirectional"))
      (node (ref "J8") (pin "2") (pinfunction "2_2") (pintype "bidirectional"))
      (node (ref "J8") (pin "4") (pinfunction "4_4") (pintype "bidirectional"))
      (node (ref "J9") (pin "1") (pinfunction "1_1") (pintype "bidirectional"))
      (node (ref "J9") (pin "3") (pinfunction "3_3") (pintype "bidirectional"))
      (node (ref "J9") (pin "5") (pinfunction "5_5") (pintype "bidirectional"))
      (node (ref "PROGRAMATOR") (pin "4") (pinfunction "4_4") (pintype "bidirectional"))
      (node (ref "R4") (pin "1") (pinfunction "1_1") (pintype "passive"))
      (node (ref "U1") (pin "4") (pinfunction "LE_4") (pintype "input"))
      (node (ref "U1") (pin "5") (pinfunction "E1_5") (pintype "input"))
      (node (ref "U1") (pin "8") (pinfunction "GND_8") (pintype "power_in"))
    )
    (net (code "34") (name "Net-(C1-Pad1)") (class "Default")
      (node (ref "C1") (pin "1") (pinfunction "1_1") (pintype "passive"))
      (node (ref "R1") (pin "1") (pinfunction "1_1") (pintype "passive"))
      (node (ref "R2") (pin "1") (pinfunction "1_1") (pintype "passive"))
    )
    (net (code "35") (name "Net-(C2-Pad2)") (class "Default")
      (node (ref "C2") (pin "2") (pinfunction "2_2") (pintype "passive"))
      (node (ref "C3") (pin "2") (pinfunction "2_2") (pintype "passive"))
      (node (ref "IC1") (pin "13") (pinfunction "VDD_13") (pintype "power_in"))
      (node (ref "IC1") (pin "28") (pinfunction "VDD_28") (pintype "power_in"))
      (node (ref "PROG_VDD") (pin "2") (pinfunction "2_2") (pintype "bidirectional"))
    )
    (net (code "36") (name "Net-(C10-Pad2)") (class "Default")
      (node (ref "C10") (pin "2") (pinfunction "2_2") (pintype "passive"))
      (node (ref "J1") (pin "2") (pinfunction "2_2") (pintype "bidirectional"))
      (node (ref "R11") (pin "2") (pinfunction "2_2") (pintype "passive"))
    )
    (net (code "37") (name "Net-(C11-Pad2)") (class "Default")
      (node (ref "C11") (pin "2") (pinfunction "2_2") (pintype "passive"))
      (node (ref "J1") (pin "3") (pinfunction "3_3") (pintype "bidirectional"))
      (node (ref "R12") (pin "2") (pinfunction "2_2") (pintype "passive"))
    )
    (net (code "38") (name "Net-(IC1-AN9{slash}PMCS1{slash}CN11{slash}RP15{slash}RB15)") (class "Default")
      (node (ref "I2C_SPI") (pin "4") (pinfunction "4_4") (pintype "bidirectional"))
      (node (ref "IC1") (pin "26") (pinfunction "AN9/PMCS1/CN11/RP15/RB15_26") (pintype "bidirectional"))
      (node (ref "R9") (pin "2") (pinfunction "2_2") (pintype "passive"))
    )
    (net (code "39") (name "Net-(IC1-AN10{slash}CVREF{slash}RTCC{slash}PMWR{slash}CN12{slash}RP14{slash}RB14)") (class "Default")
      (node (ref "I2C_SPI") (pin "3") (pinfunction "3_3") (pintype "bidirectional"))
      (node (ref "IC1") (pin "25") (pinfunction "AN10/CVREF/RTCC/PMWR/CN12/RP14/RB14_25") (pintype "bidirectional"))
      (node (ref "R10") (pin "2") (pinfunction "2_2") (pintype "passive"))
    )
    (net (code "40") (name "Net-(IC1-AN11{slash}PMRD{slash}CN13{slash}RP13{slash}RB13)") (class "Default")
      (node (ref "I2C_SPI") (pin "2") (pinfunction "2_2") (pintype "bidirectional"))
      (node (ref "IC1") (pin "24") (pinfunction "AN11/PMRD/CN13/RP13/RB13_24") (pintype "bidirectional"))
    )
    (net (code "41") (name "Net-(IC1-AN12{slash}PMD0{slash}CN14{slash}RP12{slash}RB12)") (class "Default")
      (node (ref "I2C_SPI") (pin "1") (pinfunction "1_1") (pintype "bidirectional"))
      (node (ref "IC1") (pin "23") (pinfunction "AN12/PMD0/CN14/RP12/RB12_23") (pintype "bidirectional"))
    )
    (net (code "42") (name "Net-(IC1-INT0{slash}PMD5{slash}CN23{slash}RP7{slash}RB7)") (class "Default")
      (node (ref "IC1") (pin "16") (pinfunction "INT0/PMD5/CN23/RP7/RB7_16") (pintype "bidirectional"))
      (node (ref "J9") (pin "4") (pinfunction "4_4") (pintype "bidirectional"))
      (node (ref "R8") (pin "1") (pinfunction "1_1") (pintype "passive"))
    )
    (net (code "43") (name "Net-(IC1-PGEC1{slash}AN3{slash}C2IN+{slash}CN5{slash}RP1{slash}RB1)") (class "Default")
      (node (ref "IC1") (pin "5") (pinfunction "PGEC1/AN3/C2IN+/CN5/RP1/RB1_5") (pintype "bidirectional"))
      (node (ref "IC3") (pin "5") (pinfunction "D1_5") (pintype "bidirectional"))
      (node (ref "IC4") (pin "5") (pinfunction "D1_5") (pintype "bidirectional"))
      (node (ref "IC5") (pin "5") (pinfunction "D1_5") (pintype "bidirectional"))
      (node (ref "IC6") (pin "5") (pinfunction "D1_5") (pintype "bidirectional"))
      (node (ref "IC7") (pin "5") (pinfunction "D1_5") (pintype "bidirectional"))
      (node (ref "IC8") (pin "5") (pinfunction "D1_5") (pintype "bidirectional"))
    )
    (net (code "44") (name "Net-(IC1-PGEC2{slash}TMS{slash}PMD1{slash}CN15{slash}RP11{slash}RB11)") (class "Default")
      (node (ref "IC1") (pin "22") (pinfunction "PGEC2/TMS/PMD1/CN15/RP11/RB11_22") (pintype "bidirectional"))
      (node (ref "PGEC_GP") (pin "2") (pinfunction "2_2") (pintype "bidirectional"))
    )
    (net (code "45") (name "Net-(IC1-PGEC3{slash}ASCL1{slash}PMD6{slash}CN24{slash}RP6{slash}RB6)") (class "Default")
      (node (ref "IC1") (pin "15") (pinfunction "PGEC3/ASCL1/PMD6/CN24/RP6/RB6_15") (pintype "bidirectional"))
      (node (ref "U1") (pin "3") (pinfunction "A2_3") (pintype "input"))
    )
    (net (code "46") (name "Net-(IC1-PGED1{slash}AN2{slash}C2IN-{slash}CN4{slash}RP0{slash}RB0)") (class "Default")
      (node (ref "IC1") (pin "4") (pinfunction "PGED1/AN2/C2IN-/CN4/RP0/RB0_4") (pintype "bidirectional"))
      (node (ref "IC3") (pin "4") (pinfunction "D0_4") (pintype "bidirectional"))
      (node (ref "IC4") (pin "4") (pinfunction "D0_4") (pintype "bidirectional"))
      (node (ref "IC5") (pin "4") (pinfunction "D0_4") (pintype "bidirectional"))
      (node (ref "IC6") (pin "4") (pinfunction "D0_4") (pintype "bidirectional"))
      (node (ref "IC7") (pin "4") (pinfunction "D0_4") (pintype "bidirectional"))
      (node (ref "IC8") (pin "4") (pinfunction "D0_4") (pintype "bidirectional"))
    )
    (net (code "47") (name "Net-(IC1-PGED2{slash}TDI{slash}PMD2{slash}CN16{slash}RP10{slash}RB10)") (class "Default")
      (node (ref "IC1") (pin "21") (pinfunction "PGED2/TDI/PMD2/CN16/RP10/RB10_21") (pintype "bidirectional"))
      (node (ref "PROGRAMATOR") (pin "1") (pinfunction "1_1") (pintype "bidirectional"))
    )
    (net (code "48") (name "Net-(IC1-PGED3{slash}ASDA1{slash}PMD7{slash}CN27{slash}RP5{slash}RB5)") (class "Default")
      (node (ref "IC1") (pin "14") (pinfunction "PGED3/ASDA1/PMD7/CN27/RP5/RB5_14") (pintype "bidirectional"))
      (node (ref "U1") (pin "2") (pinfunction "A1_2") (pintype "input"))
    )
    (net (code "49") (name "Net-(IC1-RA0{slash}CN2{slash}VR+{slash}AN0)") (class "Default")
      (node (ref "IC1") (pin "2") (pinfunction "RA0/CN2/VR+/AN0_2") (pintype "bidirectional"))
      (node (ref "J9") (pin "2") (pinfunction "2_2") (pintype "bidirectional"))
      (node (ref "R7") (pin "2") (pinfunction "2_2") (pintype "passive"))
    )
    (net (code "50") (name "Net-(IC1-RA1{slash}CN3{slash}VR-{slash}AN1)") (class "Default")
      (node (ref "IC1") (pin "3") (pinfunction "RA1/CN3/VR-/AN1_3") (pintype "bidirectional"))
      (node (ref "J8") (pin "5") (pinfunction "5_5") (pintype "bidirectional"))
      (node (ref "R6") (pin "2") (pinfunction "2_2") (pintype "passive"))
    )
    (net (code "51") (name "Net-(IC1-RA2{slash}CN30{slash}CKLI{slash}OSCI)") (class "Default")
      (node (ref "C6") (pin "2") (pinfunction "2_2") (pintype "passive"))
      (node (ref "IC1") (pin "9") (pinfunction "RA2/CN30/CKLI/OSCI_9") (pintype "bidirectional"))
      (node (ref "Q1") (pin "1") (pinfunction "1_1") (pintype "passive"))
    )
    (net (code "52") (name "Net-(IC1-RA3{slash}CN29{slash}PMA0{slash}CLKO{slash}OSCO)") (class "Default")
      (node (ref "C8") (pin "2") (pinfunction "2_2") (pintype "passive"))
      (node (ref "IC1") (pin "10") (pinfunction "RA3/CN29/PMA0/CLKO/OSCO_10") (pintype "bidirectional"))
      (node (ref "Q1") (pin "2") (pinfunction "2_2") (pintype "passive"))
    )
    (net (code "53") (name "Net-(IC1-RA4{slash}CN0{slash}PMA1{slash}T1CK{slash}SOSCO)") (class "Default")
      (node (ref "IC1") (pin "12") (pinfunction "RA4/CN0/PMA1/T1CK/SOSCO_12") (pintype "bidirectional"))
      (node (ref "J8") (pin "3") (pinfunction "3_3") (pintype "bidirectional"))
      (node (ref "R5") (pin "2") (pinfunction "2_2") (pintype "passive"))
    )
    (net (code "54") (name "Net-(IC1-SCL2{slash}AN5{slash}C1IN+{slash}CN7{slash}RP3{slash}RB3)") (class "Default")
      (node (ref "IC1") (pin "7") (pinfunction "SCL2/AN5/C1IN+/CN7/RP3/RB3_7") (pintype "bidirectional"))
      (node (ref "IC3") (pin "13") (pinfunction "D3_13") (pintype "bidirectional"))
      (node (ref "IC4") (pin "13") (pinfunction "D3_13") (pintype "bidirectional"))
      (node (ref "IC5") (pin "13") (pinfunction "D3_13") (pintype "bidirectional"))
      (node (ref "IC6") (pin "13") (pinfunction "D3_13") (pintype "bidirectional"))
      (node (ref "IC7") (pin "13") (pinfunction "D3_13") (pintype "bidirectional"))
      (node (ref "IC8") (pin "13") (pinfunction "D3_13") (pintype "bidirectional"))
    )
    (net (code "55") (name "Net-(IC1-SDA2{slash}AN4{slash}C1IN-{slash}CN6{slash}RP2{slash}RB2)") (class "Default")
      (node (ref "IC1") (pin "6") (pinfunction "SDA2/AN4/C1IN-/CN6/RP2/RB2_6") (pintype "bidirectional"))
      (node (ref "IC3") (pin "12") (pinfunction "D2_12") (pintype "bidirectional"))
      (node (ref "IC4") (pin "12") (pinfunction "D2_12") (pintype "bidirectional"))
      (node (ref "IC5") (pin "12") (pinfunction "D2_12") (pintype "bidirectional"))
      (node (ref "IC6") (pin "12") (pinfunction "D2_12") (pintype "bidirectional"))
      (node (ref "IC7") (pin "12") (pinfunction "D2_12") (pintype "bidirectional"))
      (node (ref "IC8") (pin "12") (pinfunction "D2_12") (pintype "bidirectional"))
    )
    (net (code "56") (name "Net-(IC1-SOSCI{slash}PMBE{slash}CN1{slash}RP4{slash}RB4)") (class "Default")
      (node (ref "IC1") (pin "11") (pinfunction "SOSCI/PMBE/CN1/RP4/RB4_11") (pintype "bidirectional"))
      (node (ref "U1") (pin "1") (pinfunction "A0_1") (pintype "input"))
    )
    (net (code "57") (name "Net-(IC1-TCK{slash}SCL1{slash}PMD4{slash}CN22{slash}RP8{slash}RB8)") (class "Default")
      (node (ref "IC1") (pin "17") (pinfunction "TCK/SCL1/PMD4/CN22/RP8/RB8_17") (pintype "bidirectional"))
      (node (ref "IC13") (pin "1") (pinfunction "TXD_1") (pintype "bidirectional"))
    )
    (net (code "58") (name "Net-(IC1-TDO{slash}SDA1{slash}PMD3{slash}CN21{slash}RP9{slash}RB9)") (class "Default")
      (node (ref "IC1") (pin "18") (pinfunction "TDO/SDA1/PMD3/CN21/RP9/RB9_18") (pintype "bidirectional"))
      (node (ref "IC13") (pin "4") (pinfunction "RXD_4") (pintype "bidirectional"))
    )
    (net (code "59") (name "Net-(IC1-VCAP{slash}VDDCORE)") (class "Default")
      (node (ref "C7") (pin "2") (pinfunction "2_2") (pintype "passive"))
      (node (ref "IC1") (pin "20") (pinfunction "VCAP/VDDCORE_20") (pintype "power_in"))
    )
    (net (code "60") (name "Net-(IC1-~{MCLR})") (class "Default")
      (node (ref "IC1") (pin "1") (pinfunction "~{MCLR}_1") (pintype "input"))
      (node (ref "PROGRAMATOR") (pin "3") (pinfunction "3_3") (pintype "bidirectional"))
      (node (ref "R2") (pin "2") (pinfunction "2_2") (pintype "passive"))
    )
    (net (code "61") (name "Net-(IC2-ADJ)") (class "Default")
      (node (ref "IC2") (pin "1") (pinfunction "ADJ_1") (pintype "input"))
      (node (ref "R3") (pin "1") (pinfunction "1_1") (pintype "passive"))
      (node (ref "R4") (pin "2") (pinfunction "2_2") (pintype "passive"))
    )
    (net (code "62") (name "Net-(IC9-OUT1)") (class "Default")
      (node (ref "IC9") (pin "16") (pinfunction "OUT1_16") (pintype "bidirectional"))
      (node (ref "MOTOR1") (pin "1") (pinfunction "1_1") (pintype "bidirectional"))
    )
    (net (code "63") (name "Net-(IC9-OUT2)") (class "Default")
      (node (ref "IC9") (pin "15") (pinfunction "OUT2_15") (pintype "bidirectional"))
      (node (ref "MOTOR1") (pin "2") (pinfunction "2_2") (pintype "bidirectional"))
    )
    (net (code "64") (name "Net-(IC9-OUT3)") (class "Default")
      (node (ref "IC9") (pin "14") (pinfunction "OUT3_14") (pintype "bidirectional"))
      (node (ref "MOTOR1") (pin "3") (pinfunction "3_3") (pintype "bidirectional"))
    )
    (net (code "65") (name "Net-(IC9-OUT4)") (class "Default")
      (node (ref "IC9") (pin "13") (pinfunction "OUT4_13") (pintype "bidirectional"))
      (node (ref "MOTOR1") (pin "4") (pinfunction "4_4") (pintype "bidirectional"))
    )
    (net (code "66") (name "Net-(IC9-OUT5)") (class "Default")
      (node (ref "IC9") (pin "12") (pinfunction "OUT5_12") (pintype "bidirectional"))
      (node (ref "MOTOR2") (pin "1") (pinfunction "1_1") (pintype "bidirectional"))
    )
    (net (code "67") (name "Net-(IC9-OUT6)") (class "Default")
      (node (ref "IC9") (pin "11") (pinfunction "OUT6_11") (pintype "bidirectional"))
      (node (ref "MOTOR2") (pin "2") (pinfunction "2_2") (pintype "bidirectional"))
    )
    (net (code "68") (name "Net-(IC9-OUT7)") (class "Default")
      (node (ref "IC9") (pin "10") (pinfunction "OUT7_10") (pintype "bidirectional"))
      (node (ref "MOTOR2") (pin "3") (pinfunction "3_3") (pintype "bidirectional"))
    )
    (net (code "69") (name "Net-(IC10-OUT1)") (class "Default")
      (node (ref "IC10") (pin "16") (pinfunction "OUT1_16") (pintype "bidirectional"))
      (node (ref "MOTOR2") (pin "4") (pinfunction "4_4") (pintype "bidirectional"))
    )
    (net (code "70") (name "Net-(IC10-OUT2)") (class "Default")
      (node (ref "IC10") (pin "15") (pinfunction "OUT2_15") (pintype "bidirectional"))
      (node (ref "MOTOR3") (pin "1") (pinfunction "1_1") (pintype "bidirectional"))
    )
    (net (code "71") (name "Net-(IC10-OUT3)") (class "Default")
      (node (ref "IC10") (pin "14") (pinfunction "OUT3_14") (pintype "bidirectional"))
      (node (ref "MOTOR3") (pin "2") (pinfunction "2_2") (pintype "bidirectional"))
    )
    (net (code "72") (name "Net-(IC10-OUT4)") (class "Default")
      (node (ref "IC10") (pin "13") (pinfunction "OUT4_13") (pintype "bidirectional"))
      (node (ref "MOTOR3") (pin "3") (pinfunction "3_3") (pintype "bidirectional"))
    )
    (net (code "73") (name "Net-(IC10-OUT5)") (class "Default")
      (node (ref "IC10") (pin "12") (pinfunction "OUT5_12") (pintype "bidirectional"))
      (node (ref "MOTOR3") (pin "4") (pinfunction "4_4") (pintype "bidirectional"))
    )
    (net (code "74") (name "Net-(IC10-OUT6)") (class "Default")
      (node (ref "IC10") (pin "11") (pinfunction "OUT6_11") (pintype "bidirectional"))
      (node (ref "MOTOR4") (pin "1") (pinfunction "1_1") (pintype "bidirectional"))
    )
    (net (code "75") (name "Net-(IC10-OUT7)") (class "Default")
      (node (ref "IC10") (pin "10") (pinfunction "OUT7_10") (pintype "bidirectional"))
      (node (ref "MOTOR4") (pin "2") (pinfunction "2_2") (pintype "bidirectional"))
    )
    (net (code "76") (name "Net-(IC11-OUT1)") (class "Default")
      (node (ref "IC11") (pin "16") (pinfunction "OUT1_16") (pintype "bidirectional"))
      (node (ref "MOTOR4") (pin "3") (pinfunction "3_3") (pintype "bidirectional"))
    )
    (net (code "77") (name "Net-(IC11-OUT2)") (class "Default")
      (node (ref "IC11") (pin "15") (pinfunction "OUT2_15") (pintype "bidirectional"))
      (node (ref "MOTOR4") (pin "4") (pinfunction "4_4") (pintype "bidirectional"))
    )
    (net (code "78") (name "Net-(IC11-OUT3)") (class "Default")
      (node (ref "IC11") (pin "14") (pinfunction "OUT3_14") (pintype "bidirectional"))
      (node (ref "MOTOR5") (pin "1") (pinfunction "1_1") (pintype "bidirectional"))
    )
    (net (code "79") (name "Net-(IC11-OUT4)") (class "Default")
      (node (ref "IC11") (pin "13") (pinfunction "OUT4_13") (pintype "bidirectional"))
      (node (ref "MOTOR5") (pin "2") (pinfunction "2_2") (pintype "bidirectional"))
    )
    (net (code "80") (name "Net-(IC11-OUT5)") (class "Default")
      (node (ref "IC11") (pin "12") (pinfunction "OUT5_12") (pintype "bidirectional"))
      (node (ref "MOTOR5") (pin "3") (pinfunction "3_3") (pintype "bidirectional"))
    )
    (net (code "81") (name "Net-(IC11-OUT6)") (class "Default")
      (node (ref "IC11") (pin "11") (pinfunction "OUT6_11") (pintype "bidirectional"))
      (node (ref "MOTOR5") (pin "4") (pinfunction "4_4") (pintype "bidirectional"))
    )
    (net (code "82") (name "Net-(IC11-OUT7)") (class "Default")
      (node (ref "IC11") (pin "10") (pinfunction "OUT7_10") (pintype "bidirectional"))
      (node (ref "MOTOR6") (pin "1") (pinfunction "1_1") (pintype "bidirectional"))
    )
    (net (code "83") (name "Net-(IC12-OUT1)") (class "Default")
      (node (ref "IC12") (pin "16") (pinfunction "OUT1_16") (pintype "bidirectional"))
      (node (ref "MOTOR6") (pin "2") (pinfunction "2_2") (pintype "bidirectional"))
    )
    (net (code "84") (name "Net-(IC12-OUT2)") (class "Default")
      (node (ref "IC12") (pin "15") (pinfunction "OUT2_15") (pintype "bidirectional"))
      (node (ref "MOTOR6") (pin "3") (pinfunction "3_3") (pintype "bidirectional"))
    )
    (net (code "85") (name "Net-(IC12-OUT3)") (class "Default")
      (node (ref "IC12") (pin "14") (pinfunction "OUT3_14") (pintype "bidirectional"))
      (node (ref "MOTOR6") (pin "4") (pinfunction "4_4") (pintype "bidirectional"))
    )
    (net (code "86") (name "Net-(IC13-3V3OUT)") (class "Default")
      (node (ref "C9") (pin "2") (pinfunction "2_2") (pintype "passive"))
      (node (ref "IC13") (pin "10") (pinfunction "3V3OUT_10") (pintype "bidirectional"))
      (node (ref "IC13") (pin "11") (pinfunction "RESET#_11") (pintype "bidirectional"))
      (node (ref "IC13") (pin "3") (pinfunction "VCCIO_3") (pintype "bidirectional"))
    )
    (net (code "87") (name "Net-(IC13-USBDM)") (class "Default")
      (node (ref "IC13") (pin "9") (pinfunction "USBDM_9") (pintype "bidirectional"))
      (node (ref "R11") (pin "1") (pinfunction "1_1") (pintype "passive"))
    )
    (net (code "88") (name "Net-(IC13-USBDP)") (class "Default")
      (node (ref "IC13") (pin "8") (pinfunction "USBDP_8") (pintype "bidirectional"))
      (node (ref "R12") (pin "1") (pinfunction "1_1") (pintype "passive"))
    )
    (net (code "89") (name "Net-(J8-Pad1)") (class "Default")
      (node (ref "J8") (pin "1") (pinfunction "1_1") (pintype "bidirectional"))
      (node (ref "PGEC_GP") (pin "3") (pinfunction "3_3") (pintype "bidirectional"))
      (node (ref "R13") (pin "2") (pinfunction "2_2") (pintype "passive"))
    )
    (net (code "90") (name "Net-(PGEC_GP-Pad1)") (class "Default")
      (node (ref "PGEC_GP") (pin "1") (pinfunction "1_1") (pintype "bidirectional"))
      (node (ref "PROGRAMATOR") (pin "2") (pinfunction "2_2") (pintype "bidirectional"))
    )
    (net (code "91") (name "Net-(PROGRAMATOR-Pad5)") (class "Default")
      (node (ref "PROGRAMATOR") (pin "5") (pinfunction "5_5") (pintype "bidirectional"))
      (node (ref "PROG_VDD") (pin "1") (pinfunction "1_1") (pintype "bidirectional"))
    )
    (net (code "92") (name "unconnected-(C13-Pad1)") (class "Default")
      (node (ref "C13") (pin "1") (pinfunction "1_1") (pintype "passive"))
    )
    (net (code "93") (name "unconnected-(C15-Pad1)") (class "Default")
      (node (ref "C15") (pin "1") (pinfunction "1_1") (pintype "passive"))
    )
    (net (code "94") (name "unconnected-(C16-Pad1)") (class "Default")
      (node (ref "C16") (pin "1") (pinfunction "1_1") (pintype "passive"))
    )
    (net (code "95") (name "unconnected-(C17-Pad1)") (class "Default")
      (node (ref "C17") (pin "1") (pinfunction "1_1") (pintype "passive"))
    )
    (net (code "96") (name "unconnected-(C18-Pad1)") (class "Default")
      (node (ref "C18") (pin "1") (pinfunction "1_1") (pintype "passive"))
    )
    (net (code "97") (name "unconnected-(C19-Pad1)") (class "Default")
      (node (ref "C19") (pin "1") (pinfunction "1_1") (pintype "passive"))
    )
    (net (code "98") (name "unconnected-(IC3-~{Q0}-Pad3)") (class "Default")
      (node (ref "IC3") (pin "3") (pinfunction "~{Q0}_3") (pintype "bidirectional"))
    )
    (net (code "99") (name "unconnected-(IC3-~{Q1}-Pad6)") (class "Default")
      (node (ref "IC3") (pin "6") (pinfunction "~{Q1}_6") (pintype "bidirectional"))
    )
    (net (code "100") (name "unconnected-(IC3-~{Q2}-Pad11)") (class "Default")
      (node (ref "IC3") (pin "11") (pinfunction "~{Q2}_11") (pintype "bidirectional"))
    )
    (net (code "101") (name "unconnected-(IC3-~{Q3}-Pad14)") (class "Default")
      (node (ref "IC3") (pin "14") (pinfunction "~{Q3}_14") (pintype "bidirectional"))
    )
    (net (code "102") (name "unconnected-(IC4-~{Q0}-Pad3)") (class "Default")
      (node (ref "IC4") (pin "3") (pinfunction "~{Q0}_3") (pintype "bidirectional"))
    )
    (net (code "103") (name "unconnected-(IC4-~{Q1}-Pad6)") (class "Default")
      (node (ref "IC4") (pin "6") (pinfunction "~{Q1}_6") (pintype "bidirectional"))
    )
    (net (code "104") (name "unconnected-(IC4-~{Q2}-Pad11)") (class "Default")
      (node (ref "IC4") (pin "11") (pinfunction "~{Q2}_11") (pintype "bidirectional"))
    )
    (net (code "105") (name "unconnected-(IC4-~{Q3}-Pad14)") (class "Default")
      (node (ref "IC4") (pin "14") (pinfunction "~{Q3}_14") (pintype "bidirectional"))
    )
    (net (code "106") (name "unconnected-(IC5-~{Q0}-Pad3)") (class "Default")
      (node (ref "IC5") (pin "3") (pinfunction "~{Q0}_3") (pintype "bidirectional"))
    )
    (net (code "107") (name "unconnected-(IC5-~{Q1}-Pad6)") (class "Default")
      (node (ref "IC5") (pin "6") (pinfunction "~{Q1}_6") (pintype "bidirectional"))
    )
    (net (code "108") (name "unconnected-(IC5-~{Q2}-Pad11)") (class "Default")
      (node (ref "IC5") (pin "11") (pinfunction "~{Q2}_11") (pintype "bidirectional"))
    )
    (net (code "109") (name "unconnected-(IC5-~{Q3}-Pad14)") (class "Default")
      (node (ref "IC5") (pin "14") (pinfunction "~{Q3}_14") (pintype "bidirectional"))
    )
    (net (code "110") (name "unconnected-(IC6-~{Q0}-Pad3)") (class "Default")
      (node (ref "IC6") (pin "3") (pinfunction "~{Q0}_3") (pintype "bidirectional"))
    )
    (net (code "111") (name "unconnected-(IC6-~{Q1}-Pad6)") (class "Default")
      (node (ref "IC6") (pin "6") (pinfunction "~{Q1}_6") (pintype "bidirectional"))
    )
    (net (code "112") (name "unconnected-(IC6-~{Q2}-Pad11)") (class "Default")
      (node (ref "IC6") (pin "11") (pinfunction "~{Q2}_11") (pintype "bidirectional"))
    )
    (net (code "113") (name "unconnected-(IC6-~{Q3}-Pad14)") (class "Default")
      (node (ref "IC6") (pin "14") (pinfunction "~{Q3}_14") (pintype "bidirectional"))
    )
    (net (code "114") (name "unconnected-(IC7-~{Q0}-Pad3)") (class "Default")
      (node (ref "IC7") (pin "3") (pinfunction "~{Q0}_3") (pintype "bidirectional"))
    )
    (net (code "115") (name "unconnected-(IC7-~{Q1}-Pad6)") (class "Default")
      (node (ref "IC7") (pin "6") (pinfunction "~{Q1}_6") (pintype "bidirectional"))
    )
    (net (code "116") (name "unconnected-(IC7-~{Q2}-Pad11)") (class "Default")
      (node (ref "IC7") (pin "11") (pinfunction "~{Q2}_11") (pintype "bidirectional"))
    )
    (net (code "117") (name "unconnected-(IC7-~{Q3}-Pad14)") (class "Default")
      (node (ref "IC7") (pin "14") (pinfunction "~{Q3}_14") (pintype "bidirectional"))
    )
    (net (code "118") (name "unconnected-(IC8-~{Q0}-Pad3)") (class "Default")
      (node (ref "IC8") (pin "3") (pinfunction "~{Q0}_3") (pintype "bidirectional"))
    )
    (net (code "119") (name "unconnected-(IC8-~{Q1}-Pad6)") (class "Default")
      (node (ref "IC8") (pin "6") (pinfunction "~{Q1}_6") (pintype "bidirectional"))
    )
    (net (code "120") (name "unconnected-(IC8-~{Q2}-Pad11)") (class "Default")
      (node (ref "IC8") (pin "11") (pinfunction "~{Q2}_11") (pintype "bidirectional"))
    )
    (net (code "121") (name "unconnected-(IC8-~{Q3}-Pad14)") (class "Default")
      (node (ref "IC8") (pin "14") (pinfunction "~{Q3}_14") (pintype "bidirectional"))
    )
    (net (code "122") (name "unconnected-(IC12-IN4-Pad4)") (class "Default")
      (node (ref "IC12") (pin "4") (pinfunction "IN4_4") (pintype "bidirectional"))
    )
    (net (code "123") (name "unconnected-(IC12-IN5-Pad5)") (class "Default")
      (node (ref "IC12") (pin "5") (pinfunction "IN5_5") (pintype "bidirectional"))
    )
    (net (code "124") (name "unconnected-(IC12-IN6-Pad6)") (class "Default")
      (node (ref "IC12") (pin "6") (pinfunction "IN6_6") (pintype "bidirectional"))
    )
    (net (code "125") (name "unconnected-(IC12-IN7-Pad7)") (class "Default")
      (node (ref "IC12") (pin "7") (pinfunction "IN7_7") (pintype "bidirectional"))
    )
    (net (code "126") (name "unconnected-(IC12-OUT4-Pad13)") (class "Default")
      (node (ref "IC12") (pin "13") (pinfunction "OUT4_13") (pintype "bidirectional"))
    )
    (net (code "127") (name "unconnected-(IC12-OUT5-Pad12)") (class "Default")
      (node (ref "IC12") (pin "12") (pinfunction "OUT5_12") (pintype "bidirectional"))
    )
    (net (code "128") (name "unconnected-(IC12-OUT6-Pad11)") (class "Default")
      (node (ref "IC12") (pin "11") (pinfunction "OUT6_11") (pintype "bidirectional"))
    )
    (net (code "129") (name "unconnected-(IC12-OUT7-Pad10)") (class "Default")
      (node (ref "IC12") (pin "10") (pinfunction "OUT7_10") (pintype "bidirectional"))
    )
    (net (code "130") (name "unconnected-(IC13-CBUS0-Pad15)") (class "Default")
      (node (ref "IC13") (pin "15") (pinfunction "CBUS0_15") (pintype "bidirectional"))
    )
    (net (code "131") (name "unconnected-(IC13-CBUS1-Pad14)") (class "Default")
      (node (ref "IC13") (pin "14") (pinfunction "CBUS1_14") (pintype "bidirectional"))
    )
    (net (code "132") (name "unconnected-(IC13-CBUS2-Pad7)") (class "Default")
      (node (ref "IC13") (pin "7") (pinfunction "CBUS2_7") (pintype "bidirectional"))
    )
    (net (code "133") (name "unconnected-(IC13-CBUS3-Pad16)") (class "Default")
      (node (ref "IC13") (pin "16") (pinfunction "CBUS3_16") (pintype "bidirectional"))
    )
    (net (code "134") (name "unconnected-(IC13-CTS#-Pad6)") (class "Default")
      (node (ref "IC13") (pin "6") (pinfunction "CTS#_6") (pintype "bidirectional"))
    )
    (net (code "135") (name "unconnected-(IC13-RTS#-Pad2)") (class "Default")
      (node (ref "IC13") (pin "2") (pinfunction "RTS#_2") (pintype "bidirectional"))
    )
    (net (code "136") (name "unconnected-(J1-Pad1)") (class "Default")
      (node (ref "J1") (pin "1") (pinfunction "1_1") (pintype "bidirectional"))
    )
    (net (code "137") (name "unconnected-(U1-Y6-Pad9)") (class "Default")
      (node (ref "U1") (pin "9") (pinfunction "Y6_9") (pintype "output"))
    )
    (net (code "138") (name "unconnected-(U1-Y7-Pad7)") (class "Default")
      (node (ref "U1") (pin "7") (pinfunction "Y7_7") (pintype "output"))
    )
  )
)
